# Schematic_Day4.net
KiCad netlist of a schematic drawn in EAGLE
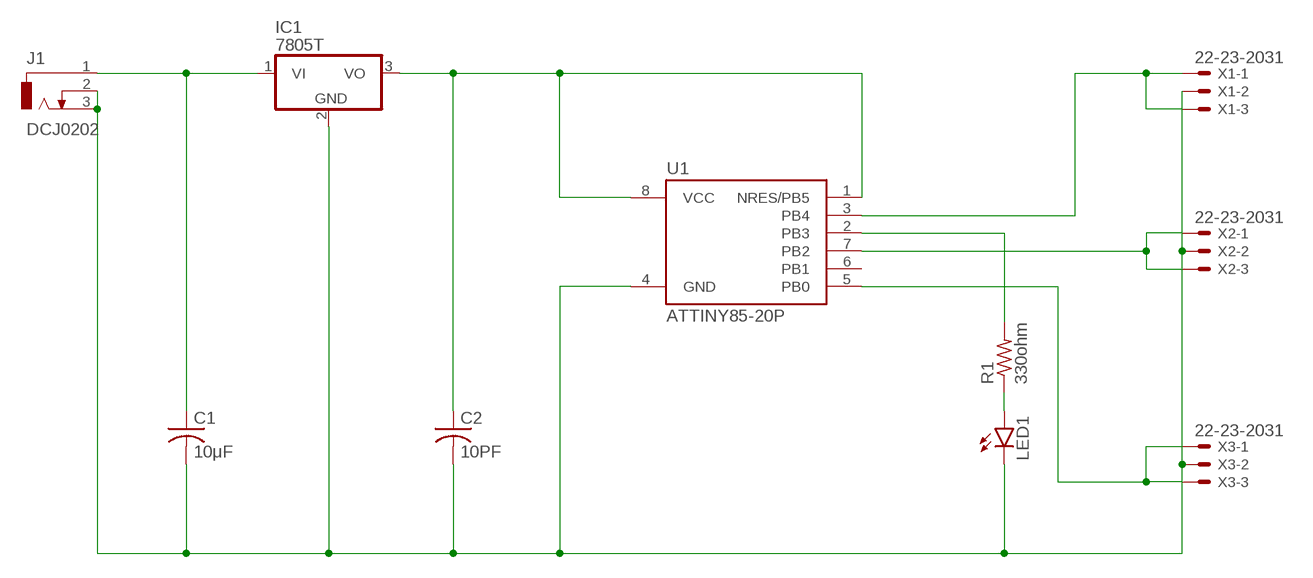
[diagram p0: schematic, sheet 1]

(export (version "E")
  (design (tool "Eeschema 10.0.6"))
  (components
    (comp (ref "C1")
      (value "10μF")
      (footprint "eagle-import:C025-024X044")
      (libsource (lib "eagle-import") (part "C-US025-024X044"))
    )
    (comp (ref "C2")
      (value "10PF")
      (footprint "eagle-import:C025-024X044")
      (libsource (lib "eagle-import") (part "C-US025-024X044"))
    )
    (comp (ref "IC1")
      (value "7805T")
      (footprint "eagle-import:TO220H")
      (libsource (lib "eagle-import") (part "78T05"))
    )
    (comp (ref "J1")
      (value "DCJ0202")
      (footprint "eagle-import:DCJ0202")
      (libsource (lib "eagle-import") (part "DCJ0202"))
    )
    (comp (ref "LED1")
      (value "LED3MM")
      (footprint "eagle-import:LED3MM")
      (libsource (lib "eagle-import") (part "LED3MM"))
    )
    (comp (ref "R1")
      (value "330ohm")
      (footprint "eagle-import:0204_5")
      (libsource (lib "eagle-import") (part "R-US_0204/5"))
    )
    (comp (ref "U1")
      (value "ATTINY85-20P")
      (footprint "eagle-import:PDIP08_300MIL")
      (libsource (lib "eagle-import") (part "ATTINY85P-20"))
    )
    (comp (ref "X1")
      (value "22-23-2031")
      (footprint "eagle-import:22-23-2031")
      (fields (field (name "MF") "MOLEX"))
      (libsource (lib "eagle-import") (part "22-23-2031"))
    )
    (comp (ref "X2")
      (value "22-23-2031")
      (footprint "eagle-import:22-23-2031")
      (fields (field (name "MF") "MOLEX"))
      (libsource (lib "eagle-import") (part "22-23-2031"))
    )
    (comp (ref "X3")
      (value "22-23-2031")
      (footprint "eagle-import:22-23-2031")
      (fields (field (name "MF") "MOLEX"))
      (libsource (lib "eagle-import") (part "22-23-2031"))
    )
  )
  (nets
    (net (code "1") (name "Net-(IC1-GND)") (class "Default")
      (node (ref "C1") (pin "2") (pinfunction "2_2") (pintype "passive"))
      (node (ref "C2") (pin "2") (pinfunction "2_2") (pintype "passive"))
      (node (ref "IC1") (pin "2") (pinfunction "GND_2") (pintype "passive"))
      (node (ref "J1") (pin "2") (pinfunction "2_2") (pintype "passive"))
      (node (ref "J1") (pin "3") (pinfunction "3_3") (pintype "passive"))
      (node (ref "LED1") (pin "K") (pinfunction "C_K") (pintype "passive"))
      (node (ref "U1") (pin "3") (pinfunction "PB4_3") (pintype "bidirectional"))
      (node (ref "U1") (pin "4") (pinfunction "GND_4") (pintype "power_in"))
      (node (ref "U1") (pin "5") (pinfunction "PB0_5") (pintype "bidirectional"))
      (node (ref "U1") (pin "7") (pinfunction "PB2_7") (pintype "bidirectional"))
      (node (ref "X1") (pin "1") (pinfunction "S_1") (pintype "passive"))
      (node (ref "X1") (pin "2") (pinfunction "S_2") (pintype "passive"))
      (node (ref "X1") (pin "3") (pinfunction "S_3") (pintype "passive"))
      (node (ref "X2") (pin "1") (pinfunction "S_1") (pintype "passive"))
      (node (ref "X2") (pin "2") (pinfunction "S_2") (pintype "passive"))
      (node (ref "X2") (pin "3") (pinfunction "S_3") (pintype "passive"))
      (node (ref "X3") (pin "1") (pinfunction "S_1") (pintype "passive"))
      (node (ref "X3") (pin "2") (pinfunction "S_2") (pintype "passive"))
      (node (ref "X3") (pin "3") (pinfunction "S_3") (pintype "passive"))
    )
    (net (code "2") (name "Net-(IC1-VI)") (class "Default")
      (node (ref "C1") (pin "1") (pinfunction "1_1") (pintype "passive"))
      (node (ref "IC1") (pin "1") (pinfunction "VI_1") (pintype "input"))
      (node (ref "J1") (pin "1") (pinfunction "1_1") (pintype "passive"))
    )
    (net (code "3") (name "Net-(IC1-VO)") (class "Default")
      (node (ref "C2") (pin "1") (pinfunction "1_1") (pintype "passive"))
      (node (ref "IC1") (pin "3") (pinfunction "VO_3") (pintype "passive"))
      (node (ref "U1") (pin "1") (pinfunction "NRES/PB5_1") (pintype "bidirectional"))
      (node (ref "U1") (pin "8") (pinfunction "VCC_8") (pintype "power_in"))
    )
    (net (code "4") (name "Net-(LED1-PadA)") (class "Default")
      (node (ref "LED1") (pin "A") (pinfunction "A_A") (pintype "passive"))
      (node (ref "R1") (pin "1") (pinfunction "1_1") (pintype "passive"))
    )
    (net (code "5") (name "Net-(U1-PB3)") (class "Default")
      (node (ref "R1") (pin "2") (pinfunction "2_2") (pintype "passive"))
      (node (ref "U1") (pin "2") (pinfunction "PB3_2") (pintype "bidirectional"))
    )
    (net (code "6") (name "unconnected-(U1-PB1-Pad6)") (class "Default")
      (node (ref "U1") (pin "6") (pinfunction "PB1_6") (pintype "bidirectional"))
    )
  )
)
